# main.net
KiCad netlist of a schematic drawn in Altium Designer
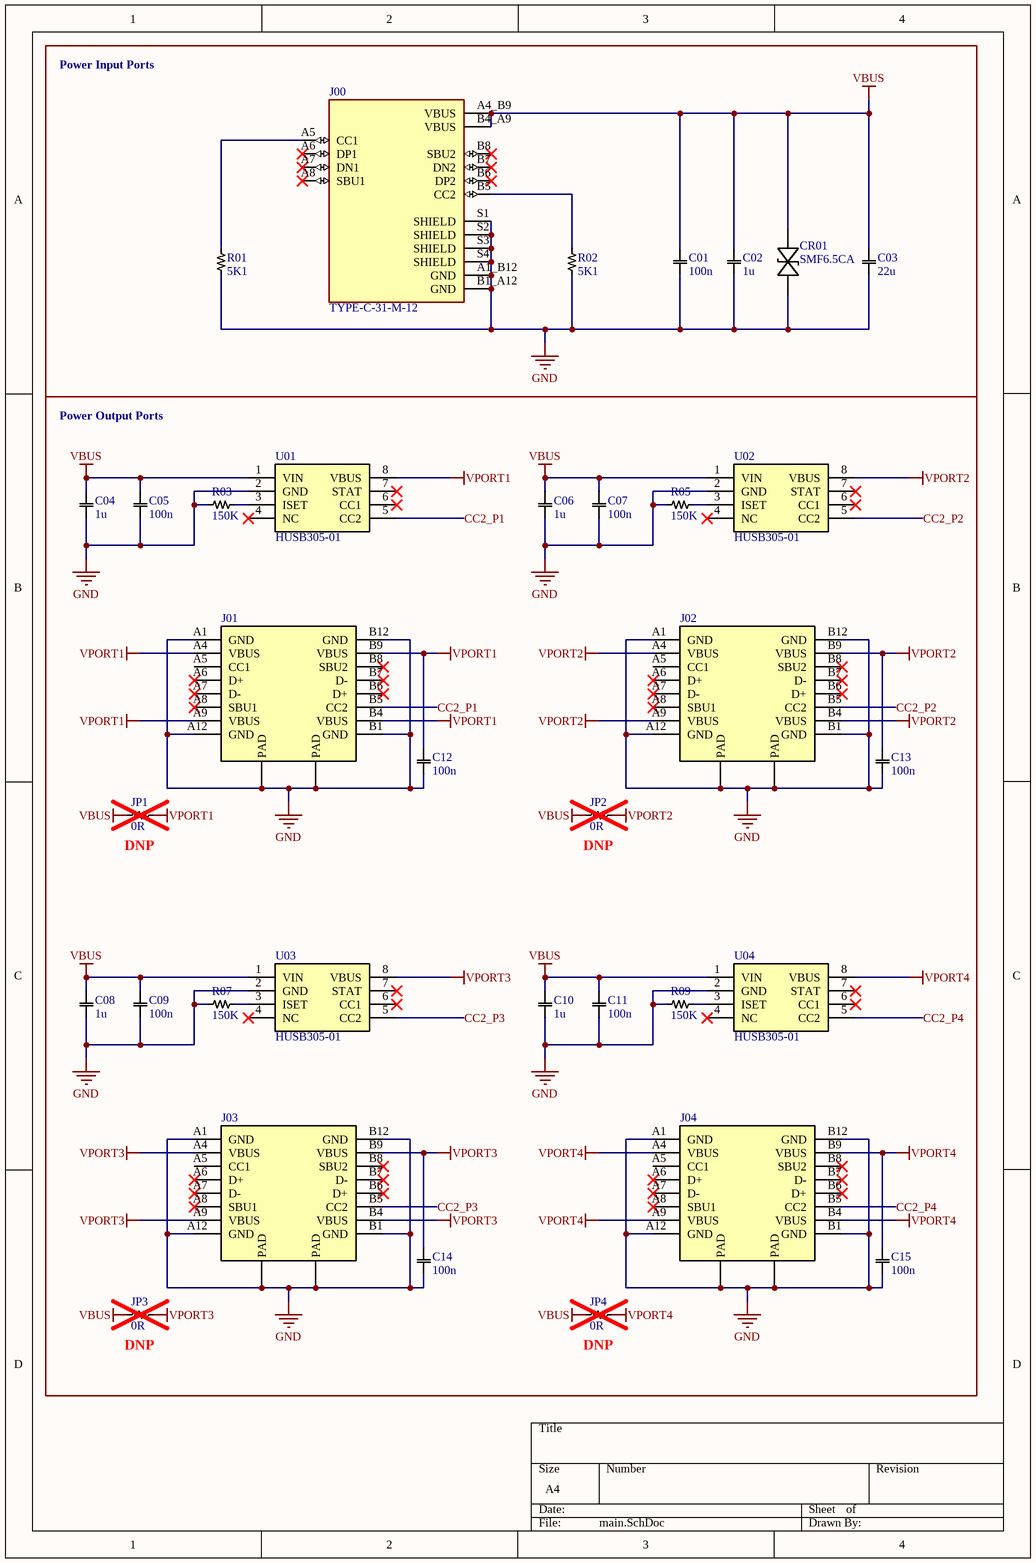
[diagram p0: main.SchDoc]

(export (version "E")
  (design (tool "Eeschema 10.0.6"))
  (components
    (comp (ref "C01")
      (value "100n")
      (footprint "RC0603N_YAG")
      (fields
        (field (name "MANUFACTURER_PART_NUMBER") "RC0603FR-0747KL")
        (field (name "COPYRIGHT") "Copyright (C) 2025 Ultra Librarian. All rights reserved.")
      )
      (libsource (lib "charge_hub_V1") (part "Capacitor"))
    )
    (comp (ref "C02")
      (value "1u")
      (footprint "RC0603N_YAG")
      (fields
        (field (name "MANUFACTURER_PART_NUMBER") "RC0603FR-0747KL")
        (field (name "COPYRIGHT") "Copyright (C) 2025 Ultra Librarian. All rights reserved.")
      )
      (libsource (lib "charge_hub_V1") (part "Capacitor"))
    )
    (comp (ref "C03")
      (value "22u")
      (footprint "RC1210")
      (fields
        (field (name "MANUFACTURER_PART_NUMBER") "RC0603FR-0747KL")
        (field (name "COPYRIGHT") "Copyright (C) 2025 Ultra Librarian. All rights reserved.")
      )
      (libsource (lib "charge_hub_V1") (part "Capacitor"))
    )
    (comp (ref "C04")
      (value "1u")
      (footprint "RC0603N_YAG")
      (fields
        (field (name "MANUFACTURER_PART_NUMBER") "RC0603FR-0747KL")
        (field (name "COPYRIGHT") "Copyright (C) 2025 Ultra Librarian. All rights reserved.")
      )
      (libsource (lib "charge_hub_V1") (part "Capacitor"))
    )
    (comp (ref "C05")
      (value "100n")
      (footprint "RC0603N_YAG")
      (fields
        (field (name "MANUFACTURER_PART_NUMBER") "RC0603FR-0747KL")
        (field (name "COPYRIGHT") "Copyright (C) 2025 Ultra Librarian. All rights reserved.")
      )
      (libsource (lib "charge_hub_V1") (part "Capacitor"))
    )
    (comp (ref "C06")
      (value "1u")
      (footprint "RC0603N_YAG")
      (fields
        (field (name "MANUFACTURER_PART_NUMBER") "RC0603FR-0747KL")
        (field (name "COPYRIGHT") "Copyright (C) 2025 Ultra Librarian. All rights reserved.")
      )
      (libsource (lib "charge_hub_V1") (part "Capacitor"))
    )
    (comp (ref "C07")
      (value "100n")
      (footprint "RC0603N_YAG")
      (fields
        (field (name "MANUFACTURER_PART_NUMBER") "RC0603FR-0747KL")
        (field (name "COPYRIGHT") "Copyright (C) 2025 Ultra Librarian. All rights reserved.")
      )
      (libsource (lib "charge_hub_V1") (part "Capacitor"))
    )
    (comp (ref "C08")
      (value "1u")
      (footprint "RC0603N_YAG")
      (fields
        (field (name "MANUFACTURER_PART_NUMBER") "RC0603FR-0747KL")
        (field (name "COPYRIGHT") "Copyright (C) 2025 Ultra Librarian. All rights reserved.")
      )
      (libsource (lib "charge_hub_V1") (part "Capacitor"))
    )
    (comp (ref "C09")
      (value "100n")
      (footprint "RC0603N_YAG")
      (fields
        (field (name "MANUFACTURER_PART_NUMBER") "RC0603FR-0747KL")
        (field (name "COPYRIGHT") "Copyright (C) 2025 Ultra Librarian. All rights reserved.")
      )
      (libsource (lib "charge_hub_V1") (part "Capacitor"))
    )
    (comp (ref "C10")
      (value "1u")
      (footprint "RC0603N_YAG")
      (fields
        (field (name "MANUFACTURER_PART_NUMBER") "RC0603FR-0747KL")
        (field (name "COPYRIGHT") "Copyright (C) 2025 Ultra Librarian. All rights reserved.")
      )
      (libsource (lib "charge_hub_V1") (part "Capacitor"))
    )
    (comp (ref "C11")
      (value "100n")
      (footprint "RC0603N_YAG")
      (fields
        (field (name "MANUFACTURER_PART_NUMBER") "RC0603FR-0747KL")
        (field (name "COPYRIGHT") "Copyright (C) 2025 Ultra Librarian. All rights reserved.")
      )
      (libsource (lib "charge_hub_V1") (part "Capacitor"))
    )
    (comp (ref "C12")
      (value "100n")
      (footprint "RC0603N_YAG")
      (fields
        (field (name "MANUFACTURER_PART_NUMBER") "RC0603FR-0747KL")
        (field (name "COPYRIGHT") "Copyright (C) 2025 Ultra Librarian. All rights reserved.")
      )
      (libsource (lib "charge_hub_V1") (part "Capacitor"))
    )
    (comp (ref "C13")
      (value "100n")
      (footprint "RC0603N_YAG")
      (fields
        (field (name "MANUFACTURER_PART_NUMBER") "RC0603FR-0747KL")
        (field (name "COPYRIGHT") "Copyright (C) 2025 Ultra Librarian. All rights reserved.")
      )
      (libsource (lib "charge_hub_V1") (part "Capacitor"))
    )
    (comp (ref "C14")
      (value "100n")
      (footprint "RC0603N_YAG")
      (fields
        (field (name "MANUFACTURER_PART_NUMBER") "RC0603FR-0747KL")
        (field (name "COPYRIGHT") "Copyright (C) 2025 Ultra Librarian. All rights reserved.")
      )
      (libsource (lib "charge_hub_V1") (part "Capacitor"))
    )
    (comp (ref "C15")
      (value "100n")
      (footprint "RC0603N_YAG")
      (fields
        (field (name "MANUFACTURER_PART_NUMBER") "RC0603FR-0747KL")
        (field (name "COPYRIGHT") "Copyright (C) 2025 Ultra Librarian. All rights reserved.")
      )
      (libsource (lib "charge_hub_V1") (part "Capacitor"))
    )
    (comp (ref "CR01")
      (value "SMF6.5CA")
      (footprint "SOD-123F_LTF")
      (description "Description")
      (fields (field (name "COPYRIGHT") "Copyright (C) 2026 Ultra Librarian. All rights reserved."))
      (libsource (lib "charge_hub_V1") (part "SMF6.5CA"))
    )
    (comp (ref "J00")
      (value "TYPE-C-31-M-12")
      (footprint "HRO_TYPE-C-31-M-12")
      (description "USB Connectors 24 Receptacle 1 8.94*7.3mm RoHS")
      (fields (field (name "MF") "HRO Electronics Co., Ltd."))
      (libsource (lib "TYPE-C-31-M-12") (part "TYPE-C-31-M-12"))
    )
    (comp (ref "J01")
      (value "TYPE-C MALE")
      (footprint "TYPE-C MALE")
      (libsource (lib "SMF6P5CA") (part "TYPE-C MALE"))
    )
    (comp (ref "J02")
      (value "TYPE-C MALE")
      (footprint "TYPE-C MALE")
      (libsource (lib "SMF6P5CA") (part "TYPE-C MALE"))
    )
    (comp (ref "J03")
      (value "TYPE-C MALE")
      (footprint "TYPE-C MALE")
      (libsource (lib "SMF6P5CA") (part "TYPE-C MALE"))
    )
    (comp (ref "J04")
      (value "TYPE-C MALE")
      (footprint "TYPE-C MALE")
      (libsource (lib "SMF6P5CA") (part "TYPE-C MALE"))
    )
    (comp (ref "JP1")
      (value "0R")
      (footprint "RC0603N_YAG")
      (description "RES SMD 47K OHM 1% 1/10W 0603")
      (fields
        (field (name "MANUFACTURER_PART_NUMBER") "RC0603FR-0747KL")
        (field (name "COPYRIGHT") "Copyright (C) 2025 Ultra Librarian. All rights reserved.")
      )
      (libsource (lib "charge_hub_V1") (part "RC0603"))
    )
    (comp (ref "JP2")
      (value "0R")
      (footprint "RC0603N_YAG")
      (description "RES SMD 47K OHM 1% 1/10W 0603")
      (fields
        (field (name "MANUFACTURER_PART_NUMBER") "RC0603FR-0747KL")
        (field (name "COPYRIGHT") "Copyright (C) 2025 Ultra Librarian. All rights reserved.")
      )
      (libsource (lib "charge_hub_V1") (part "RC0603"))
    )
    (comp (ref "JP3")
      (value "0R")
      (footprint "RC0603N_YAG")
      (description "RES SMD 47K OHM 1% 1/10W 0603")
      (fields
        (field (name "MANUFACTURER_PART_NUMBER") "RC0603FR-0747KL")
        (field (name "COPYRIGHT") "Copyright (C) 2025 Ultra Librarian. All rights reserved.")
      )
      (libsource (lib "charge_hub_V1") (part "RC0603"))
    )
    (comp (ref "JP4")
      (value "0R")
      (footprint "RC0603N_YAG")
      (description "RES SMD 47K OHM 1% 1/10W 0603")
      (fields
        (field (name "MANUFACTURER_PART_NUMBER") "RC0603FR-0747KL")
        (field (name "COPYRIGHT") "Copyright (C) 2025 Ultra Librarian. All rights reserved.")
      )
      (libsource (lib "charge_hub_V1") (part "RC0603"))
    )
    (comp (ref "R01")
      (value "5K1")
      (footprint "RC0603N_YAG")
      (description "RES SMD 47K OHM 1% 1/10W 0603")
      (fields
        (field (name "MANUFACTURER_PART_NUMBER") "RC0603FR-0747KL")
        (field (name "COPYRIGHT") "Copyright (C) 2025 Ultra Librarian. All rights reserved.")
      )
      (libsource (lib "charge_hub_V1") (part "RC0603"))
    )
    (comp (ref "R02")
      (value "5K1")
      (footprint "RC0603N_YAG")
      (description "RES SMD 47K OHM 1% 1/10W 0603")
      (fields
        (field (name "MANUFACTURER_PART_NUMBER") "RC0603FR-0747KL")
        (field (name "COPYRIGHT") "Copyright (C) 2025 Ultra Librarian. All rights reserved.")
      )
      (libsource (lib "charge_hub_V1") (part "RC0603"))
    )
    (comp (ref "R03")
      (value "150K")
      (footprint "RC0603N_YAG")
      (description "RES SMD 47K OHM 1% 1/10W 0603")
      (fields
        (field (name "MANUFACTURER_PART_NUMBER") "RC0603FR-0747KL")
        (field (name "COPYRIGHT") "Copyright (C) 2025 Ultra Librarian. All rights reserved.")
      )
      (libsource (lib "charge_hub_V1") (part "RC0603"))
    )
    (comp (ref "R05")
      (value "150K")
      (footprint "RC0603N_YAG")
      (description "RES SMD 47K OHM 1% 1/10W 0603")
      (fields
        (field (name "MANUFACTURER_PART_NUMBER") "RC0603FR-0747KL")
        (field (name "COPYRIGHT") "Copyright (C) 2025 Ultra Librarian. All rights reserved.")
      )
      (libsource (lib "charge_hub_V1") (part "RC0603"))
    )
    (comp (ref "R07")
      (value "150K")
      (footprint "RC0603N_YAG")
      (description "RES SMD 47K OHM 1% 1/10W 0603")
      (fields
        (field (name "MANUFACTURER_PART_NUMBER") "RC0603FR-0747KL")
        (field (name "COPYRIGHT") "Copyright (C) 2025 Ultra Librarian. All rights reserved.")
      )
      (libsource (lib "charge_hub_V1") (part "RC0603"))
    )
    (comp (ref "R09")
      (value "150K")
      (footprint "RC0603N_YAG")
      (description "RES SMD 47K OHM 1% 1/10W 0603")
      (fields
        (field (name "MANUFACTURER_PART_NUMBER") "RC0603FR-0747KL")
        (field (name "COPYRIGHT") "Copyright (C) 2025 Ultra Librarian. All rights reserved.")
      )
      (libsource (lib "charge_hub_V1") (part "RC0603"))
    )
    (comp (ref "U01")
      (value "HUSB305-01")
      (footprint "TSOT23-8L")
      (libsource (lib "charge_hub_V1") (part "HUSB305-01"))
    )
    (comp (ref "U02")
      (value "HUSB305-01")
      (footprint "TSOT23-8L")
      (libsource (lib "charge_hub_V1") (part "HUSB305-01"))
    )
    (comp (ref "U03")
      (value "HUSB305-01")
      (footprint "TSOT23-8L")
      (libsource (lib "charge_hub_V1") (part "HUSB305-01"))
    )
    (comp (ref "U04")
      (value "HUSB305-01")
      (footprint "TSOT23-8L")
      (libsource (lib "charge_hub_V1") (part "HUSB305-01"))
    )
  )
  (nets
    (net (code "1") (name "/CC2_P1") (class "Default")
      (node (ref "J01") (pin "B5") (pinfunction "CC2_B5") (pintype "passive"))
      (node (ref "U01") (pin "5") (pinfunction "CC2_5") (pintype "passive"))
    )
    (net (code "2") (name "/CC2_P2") (class "Default")
      (node (ref "J02") (pin "B5") (pinfunction "CC2_B5") (pintype "passive"))
      (node (ref "U02") (pin "5") (pinfunction "CC2_5") (pintype "passive"))
    )
    (net (code "3") (name "/CC2_P3") (class "Default")
      (node (ref "J03") (pin "B5") (pinfunction "CC2_B5") (pintype "passive"))
      (node (ref "U03") (pin "5") (pinfunction "CC2_5") (pintype "passive"))
    )
    (net (code "4") (name "/CC2_P4") (class "Default")
      (node (ref "J04") (pin "B5") (pinfunction "CC2_B5") (pintype "passive"))
      (node (ref "U04") (pin "5") (pinfunction "CC2_5") (pintype "passive"))
    )
    (net (code "5") (name "GND") (class "Default")
      (node (ref "C01") (pin "2") (pinfunction "2_2") (pintype "passive"))
      (node (ref "C02") (pin "2") (pinfunction "2_2") (pintype "passive"))
      (node (ref "C03") (pin "2") (pinfunction "2_2") (pintype "passive"))
      (node (ref "C04") (pin "2") (pinfunction "2_2") (pintype "passive"))
      (node (ref "C05") (pin "2") (pinfunction "2_2") (pintype "passive"))
      (node (ref "C06") (pin "2") (pinfunction "2_2") (pintype "passive"))
      (node (ref "C07") (pin "2") (pinfunction "2_2") (pintype "passive"))
      (node (ref "C08") (pin "2") (pinfunction "2_2") (pintype "passive"))
      (node (ref "C09") (pin "2") (pinfunction "2_2") (pintype "passive"))
      (node (ref "C10") (pin "2") (pinfunction "2_2") (pintype "passive"))
      (node (ref "C11") (pin "2") (pinfunction "2_2") (pintype "passive"))
      (node (ref "C12") (pin "2") (pinfunction "2_2") (pintype "passive"))
      (node (ref "C13") (pin "2") (pinfunction "2_2") (pintype "passive"))
      (node (ref "C14") (pin "2") (pinfunction "2_2") (pintype "passive"))
      (node (ref "C15") (pin "2") (pinfunction "2_2") (pintype "passive"))
      (node (ref "CR01") (pin "2") (pinfunction "2_2") (pintype "passive"))
      (node (ref "J00") (pin "A1_B12") (pinfunction "GND_A1_B12") (pintype "power_in"))
      (node (ref "J00") (pin "B1_A12") (pinfunction "GND_B1_A12") (pintype "power_in"))
      (node (ref "J00") (pin "S1") (pinfunction "SHIELD_S1") (pintype "passive"))
      (node (ref "J00") (pin "S2") (pinfunction "SHIELD_S2") (pintype "passive"))
      (node (ref "J00") (pin "S3") (pinfunction "SHIELD_S3") (pintype "passive"))
      (node (ref "J00") (pin "S4") (pinfunction "SHIELD_S4") (pintype "passive"))
      (node (ref "J01") (pin "A1") (pinfunction "GND_A1") (pintype "passive"))
      (node (ref "J01") (pin "A12") (pinfunction "GND_A12") (pintype "passive"))
      (node (ref "J01") (pin "B1") (pinfunction "GND_B1") (pintype "passive"))
      (node (ref "J01") (pin "B12") (pinfunction "GND_B12") (pintype "passive"))
      (node (ref "J01") (pin "P1") (pinfunction "PAD_P1") (pintype "passive"))
      (node (ref "J01") (pin "P2") (pinfunction "PAD_P2") (pintype "passive"))
      (node (ref "J02") (pin "A1") (pinfunction "GND_A1") (pintype "passive"))
      (node (ref "J02") (pin "A12") (pinfunction "GND_A12") (pintype "passive"))
      (node (ref "J02") (pin "B1") (pinfunction "GND_B1") (pintype "passive"))
      (node (ref "J02") (pin "B12") (pinfunction "GND_B12") (pintype "passive"))
      (node (ref "J02") (pin "P1") (pinfunction "PAD_P1") (pintype "passive"))
      (node (ref "J02") (pin "P2") (pinfunction "PAD_P2") (pintype "passive"))
      (node (ref "J03") (pin "A1") (pinfunction "GND_A1") (pintype "passive"))
      (node (ref "J03") (pin "A12") (pinfunction "GND_A12") (pintype "passive"))
      (node (ref "J03") (pin "B1") (pinfunction "GND_B1") (pintype "passive"))
      (node (ref "J03") (pin "B12") (pinfunction "GND_B12") (pintype "passive"))
      (node (ref "J03") (pin "P1") (pinfunction "PAD_P1") (pintype "passive"))
      (node (ref "J03") (pin "P2") (pinfunction "PAD_P2") (pintype "passive"))
      (node (ref "J04") (pin "A1") (pinfunction "GND_A1") (pintype "passive"))
      (node (ref "J04") (pin "A12") (pinfunction "GND_A12") (pintype "passive"))
      (node (ref "J04") (pin "B1") (pinfunction "GND_B1") (pintype "passive"))
      (node (ref "J04") (pin "B12") (pinfunction "GND_B12") (pintype "passive"))
      (node (ref "J04") (pin "P1") (pinfunction "PAD_P1") (pintype "passive"))
      (node (ref "J04") (pin "P2") (pinfunction "PAD_P2") (pintype "passive"))
      (node (ref "R01") (pin "2") (pinfunction "2_2") (pintype "passive"))
      (node (ref "R02") (pin "2") (pinfunction "2_2") (pintype "passive"))
      (node (ref "R03") (pin "1") (pinfunction "1_1") (pintype "passive"))
      (node (ref "R05") (pin "1") (pinfunction "1_1") (pintype "passive"))
      (node (ref "R07") (pin "1") (pinfunction "1_1") (pintype "passive"))
      (node (ref "R09") (pin "1") (pinfunction "1_1") (pintype "passive"))
      (node (ref "U01") (pin "2") (pinfunction "GND_2") (pintype "passive"))
      (node (ref "U02") (pin "2") (pinfunction "GND_2") (pintype "passive"))
      (node (ref "U03") (pin "2") (pinfunction "GND_2") (pintype "passive"))
      (node (ref "U04") (pin "2") (pinfunction "GND_2") (pintype "passive"))
    )
    (net (code "6") (name "Net-(J00-CC1)") (class "Default")
      (node (ref "J00") (pin "A5") (pinfunction "CC1_A5") (pintype "bidirectional"))
      (node (ref "R01") (pin "1") (pinfunction "1_1") (pintype "passive"))
    )
    (net (code "7") (name "Net-(J00-CC2)") (class "Default")
      (node (ref "J00") (pin "B5") (pinfunction "CC2_B5") (pintype "bidirectional"))
      (node (ref "R02") (pin "1") (pinfunction "1_1") (pintype "passive"))
    )
    (net (code "8") (name "Net-(U01-ISET)") (class "Default")
      (node (ref "R03") (pin "2") (pinfunction "2_2") (pintype "passive"))
      (node (ref "U01") (pin "3") (pinfunction "ISET_3") (pintype "passive"))
    )
    (net (code "9") (name "Net-(U02-ISET)") (class "Default")
      (node (ref "R05") (pin "2") (pinfunction "2_2") (pintype "passive"))
      (node (ref "U02") (pin "3") (pinfunction "ISET_3") (pintype "passive"))
    )
    (net (code "10") (name "Net-(U03-ISET)") (class "Default")
      (node (ref "R07") (pin "2") (pinfunction "2_2") (pintype "passive"))
      (node (ref "U03") (pin "3") (pinfunction "ISET_3") (pintype "passive"))
    )
    (net (code "11") (name "Net-(U04-ISET)") (class "Default")
      (node (ref "R09") (pin "2") (pinfunction "2_2") (pintype "passive"))
      (node (ref "U04") (pin "3") (pinfunction "ISET_3") (pintype "passive"))
    )
    (net (code "12") (name "VBUS") (class "Default")
      (node (ref "C01") (pin "1") (pinfunction "1_1") (pintype "passive"))
      (node (ref "C02") (pin "1") (pinfunction "1_1") (pintype "passive"))
      (node (ref "C03") (pin "1") (pinfunction "1_1") (pintype "passive"))
      (node (ref "C04") (pin "1") (pinfunction "1_1") (pintype "passive"))
      (node (ref "C05") (pin "1") (pinfunction "1_1") (pintype "passive"))
      (node (ref "C06") (pin "1") (pinfunction "1_1") (pintype "passive"))
      (node (ref "C07") (pin "1") (pinfunction "1_1") (pintype "passive"))
      (node (ref "C08") (pin "1") (pinfunction "1_1") (pintype "passive"))
      (node (ref "C09") (pin "1") (pinfunction "1_1") (pintype "passive"))
      (node (ref "C10") (pin "1") (pinfunction "1_1") (pintype "passive"))
      (node (ref "C11") (pin "1") (pinfunction "1_1") (pintype "passive"))
      (node (ref "CR01") (pin "1") (pinfunction "1_1") (pintype "passive"))
      (node (ref "J00") (pin "A4_B9") (pinfunction "VBUS_A4_B9") (pintype "power_in"))
      (node (ref "J00") (pin "B4_A9") (pinfunction "VBUS_B4_A9") (pintype "power_in"))
      (node (ref "JP1") (pin "1") (pinfunction "1_1") (pintype "passive"))
      (node (ref "JP2") (pin "1") (pinfunction "1_1") (pintype "passive"))
      (node (ref "JP3") (pin "1") (pinfunction "1_1") (pintype "passive"))
      (node (ref "JP4") (pin "1") (pinfunction "1_1") (pintype "passive"))
      (node (ref "U01") (pin "1") (pinfunction "VIN_1") (pintype "passive"))
      (node (ref "U02") (pin "1") (pinfunction "VIN_1") (pintype "passive"))
      (node (ref "U03") (pin "1") (pinfunction "VIN_1") (pintype "passive"))
      (node (ref "U04") (pin "1") (pinfunction "VIN_1") (pintype "passive"))
    )
    (net (code "13") (name "VPORT1") (class "Default")
      (node (ref "C12") (pin "1") (pinfunction "1_1") (pintype "passive"))
      (node (ref "J01") (pin "A4") (pinfunction "VBUS_A4") (pintype "passive"))
      (node (ref "J01") (pin "A9") (pinfunction "VBUS_A9") (pintype "passive"))
      (node (ref "J01") (pin "B4") (pinfunction "VBUS_B4") (pintype "passive"))
      (node (ref "J01") (pin "B9") (pinfunction "VBUS_B9") (pintype "passive"))
      (node (ref "JP1") (pin "2") (pinfunction "2_2") (pintype "passive"))
      (node (ref "U01") (pin "8") (pinfunction "VBUS_8") (pintype "passive"))
    )
    (net (code "14") (name "VPORT2") (class "Default")
      (node (ref "C13") (pin "1") (pinfunction "1_1") (pintype "passive"))
      (node (ref "J02") (pin "A4") (pinfunction "VBUS_A4") (pintype "passive"))
      (node (ref "J02") (pin "A9") (pinfunction "VBUS_A9") (pintype "passive"))
      (node (ref "J02") (pin "B4") (pinfunction "VBUS_B4") (pintype "passive"))
      (node (ref "J02") (pin "B9") (pinfunction "VBUS_B9") (pintype "passive"))
      (node (ref "JP2") (pin "2") (pinfunction "2_2") (pintype "passive"))
      (node (ref "U02") (pin "8") (pinfunction "VBUS_8") (pintype "passive"))
    )
    (net (code "15") (name "VPORT3") (class "Default")
      (node (ref "C14") (pin "1") (pinfunction "1_1") (pintype "passive"))
      (node (ref "J03") (pin "A4") (pinfunction "VBUS_A4") (pintype "passive"))
      (node (ref "J03") (pin "A9") (pinfunction "VBUS_A9") (pintype "passive"))
      (node (ref "J03") (pin "B4") (pinfunction "VBUS_B4") (pintype "passive"))
      (node (ref "J03") (pin "B9") (pinfunction "VBUS_B9") (pintype "passive"))
      (node (ref "JP3") (pin "2") (pinfunction "2_2") (pintype "passive"))
      (node (ref "U03") (pin "8") (pinfunction "VBUS_8") (pintype "passive"))
    )
    (net (code "16") (name "VPORT4") (class "Default")
      (node (ref "C15") (pin "1") (pinfunction "1_1") (pintype "passive"))
      (node (ref "J04") (pin "A4") (pinfunction "VBUS_A4") (pintype "passive"))
      (node (ref "J04") (pin "A9") (pinfunction "VBUS_A9") (pintype "passive"))
      (node (ref "J04") (pin "B4") (pinfunction "VBUS_B4") (pintype "passive"))
      (node (ref "J04") (pin "B9") (pinfunction "VBUS_B9") (pintype "passive"))
      (node (ref "JP4") (pin "2") (pinfunction "2_2") (pintype "passive"))
      (node (ref "U04") (pin "8") (pinfunction "VBUS_8") (pintype "passive"))
    )
    (net (code "17") (name "unconnected-(J00-DN1-PadA7)") (class "Default")
      (node (ref "J00") (pin "A7") (pinfunction "DN1_A7") (pintype "bidirectional+no_connect"))
    )
    (net (code "18") (name "unconnected-(J00-DN2-PadB7)") (class "Default")
      (node (ref "J00") (pin "B7") (pinfunction "DN2_B7") (pintype "bidirectional+no_connect"))
    )
    (net (code "19") (name "unconnected-(J00-DP1-PadA6)") (class "Default")
      (node (ref "J00") (pin "A6") (pinfunction "DP1_A6") (pintype "bidirectional+no_connect"))
    )
    (net (code "20") (name "unconnected-(J00-DP2-PadB6)") (class "Default")
      (node (ref "J00") (pin "B6") (pinfunction "DP2_B6") (pintype "bidirectional+no_connect"))
    )
    (net (code "21") (name "unconnected-(J00-SBU1-PadA8)") (class "Default")
      (node (ref "J00") (pin "A8") (pinfunction "SBU1_A8") (pintype "bidirectional+no_connect"))
    )
    (net (code "22") (name "unconnected-(J00-SBU2-PadB8)") (class "Default")
      (node (ref "J00") (pin "B8") (pinfunction "SBU2_B8") (pintype "bidirectional+no_connect"))
    )
    (net (code "23") (name "unconnected-(J01-CC1-PadA5)") (class "Default")
      (node (ref "J01") (pin "A5") (pinfunction "CC1_A5") (pintype "passive"))
    )
    (net (code "24") (name "unconnected-(J01-D+-PadA6)") (class "Default")
      (node (ref "J01") (pin "A6") (pinfunction "D+_A6") (pintype "passive+no_connect"))
    )
    (net (code "25") (name "unconnected-(J01-D+-PadB6)") (class "Default")
      (node (ref "J01") (pin "B6") (pinfunction "D+_B6") (pintype "passive+no_connect"))
    )
    (net (code "26") (name "unconnected-(J01-D--PadA7)") (class "Default")
      (node (ref "J01") (pin "A7") (pinfunction "D-_A7") (pintype "passive+no_connect"))
    )
    (net (code "27") (name "unconnected-(J01-D--PadB7)") (class "Default")
      (node (ref "J01") (pin "B7") (pinfunction "D-_B7") (pintype "passive+no_connect"))
    )
    (net (code "28") (name "unconnected-(J01-SBU1-PadA8)") (class "Default")
      (node (ref "J01") (pin "A8") (pinfunction "SBU1_A8") (pintype "passive+no_connect"))
    )
    (net (code "29") (name "unconnected-(J01-SBU2-PadB8)") (class "Default")
      (node (ref "J01") (pin "B8") (pinfunction "SBU2_B8") (pintype "passive+no_connect"))
    )
    (net (code "30") (name "unconnected-(J02-CC1-PadA5)") (class "Default")
      (node (ref "J02") (pin "A5") (pinfunction "CC1_A5") (pintype "passive"))
    )
    (net (code "31") (name "unconnected-(J02-D+-PadA6)") (class "Default")
      (node (ref "J02") (pin "A6") (pinfunction "D+_A6") (pintype "passive+no_connect"))
    )
    (net (code "32") (name "unconnected-(J02-D+-PadB6)") (class "Default")
      (node (ref "J02") (pin "B6") (pinfunction "D+_B6") (pintype "passive+no_connect"))
    )
    (net (code "33") (name "unconnected-(J02-D--PadA7)") (class "Default")
      (node (ref "J02") (pin "A7") (pinfunction "D-_A7") (pintype "passive+no_connect"))
    )
    (net (code "34") (name "unconnected-(J02-D--PadB7)") (class "Default")
      (node (ref "J02") (pin "B7") (pinfunction "D-_B7") (pintype "passive+no_connect"))
    )
    (net (code "35") (name "unconnected-(J02-SBU1-PadA8)") (class "Default")
      (node (ref "J02") (pin "A8") (pinfunction "SBU1_A8") (pintype "passive+no_connect"))
    )
    (net (code "36") (name "unconnected-(J02-SBU2-PadB8)") (class "Default")
      (node (ref "J02") (pin "B8") (pinfunction "SBU2_B8") (pintype "passive+no_connect"))
    )
    (net (code "37") (name "unconnected-(J03-CC1-PadA5)") (class "Default")
      (node (ref "J03") (pin "A5") (pinfunction "CC1_A5") (pintype "passive"))
    )
    (net (code "38") (name "unconnected-(J03-D+-PadA6)") (class "Default")
      (node (ref "J03") (pin "A6") (pinfunction "D+_A6") (pintype "passive+no_connect"))
    )
    (net (code "39") (name "unconnected-(J03-D+-PadB6)") (class "Default")
      (node (ref "J03") (pin "B6") (pinfunction "D+_B6") (pintype "passive+no_connect"))
    )
    (net (code "40") (name "unconnected-(J03-D--PadA7)") (class "Default")
      (node (ref "J03") (pin "A7") (pinfunction "D-_A7") (pintype "passive+no_connect"))
    )
    (net (code "41") (name "unconnected-(J03-D--PadB7)") (class "Default")
      (node (ref "J03") (pin "B7") (pinfunction "D-_B7") (pintype "passive+no_connect"))
    )
    (net (code "42") (name "unconnected-(J03-SBU1-PadA8)") (class "Default")
      (node (ref "J03") (pin "A8") (pinfunction "SBU1_A8") (pintype "passive+no_connect"))
    )
    (net (code "43") (name "unconnected-(J03-SBU2-PadB8)") (class "Default")
      (node (ref "J03") (pin "B8") (pinfunction "SBU2_B8") (pintype "passive+no_connect"))
    )
    (net (code "44") (name "unconnected-(J04-CC1-PadA5)") (class "Default")
      (node (ref "J04") (pin "A5") (pinfunction "CC1_A5") (pintype "passive"))
    )
    (net (code "45") (name "unconnected-(J04-D+-PadA6)") (class "Default")
      (node (ref "J04") (pin "A6") (pinfunction "D+_A6") (pintype "passive+no_connect"))
    )
    (net (code "46") (name "unconnected-(J04-D+-PadB6)") (class "Default")
      (node (ref "J04") (pin "B6") (pinfunction "D+_B6") (pintype "passive+no_connect"))
    )
    (net (code "47") (name "unconnected-(J04-D--PadA7)") (class "Default")
      (node (ref "J04") (pin "A7") (pinfunction "D-_A7") (pintype "passive+no_connect"))
    )
    (net (code "48") (name "unconnected-(J04-D--PadB7)") (class "Default")
      (node (ref "J04") (pin "B7") (pinfunction "D-_B7") (pintype "passive+no_connect"))
    )
    (net (code "49") (name "unconnected-(J04-SBU1-PadA8)") (class "Default")
      (node (ref "J04") (pin "A8") (pinfunction "SBU1_A8") (pintype "passive+no_connect"))
    )
    (net (code "50") (name "unconnected-(J04-SBU2-PadB8)") (class "Default")
      (node (ref "J04") (pin "B8") (pinfunction "SBU2_B8") (pintype "passive+no_connect"))
    )
    (net (code "51") (name "unconnected-(U01-CC1-Pad6)") (class "Default")
      (node (ref "U01") (pin "6") (pinfunction "CC1_6") (pintype "passive+no_connect"))
    )
    (net (code "52") (name "unconnected-(U01-NC-Pad4)") (class "Default")
      (node (ref "U01") (pin "4") (pinfunction "NC_4") (pintype "passive+no_connect"))
    )
    (net (code "53") (name "unconnected-(U01-STAT-Pad7)") (class "Default")
      (node (ref "U01") (pin "7") (pinfunction "STAT_7") (pintype "passive+no_connect"))
    )
    (net (code "54") (name "unconnected-(U02-CC1-Pad6)") (class "Default")
      (node (ref "U02") (pin "6") (pinfunction "CC1_6") (pintype "passive+no_connect"))
    )
    (net (code "55") (name "unconnected-(U02-NC-Pad4)") (class "Default")
      (node (ref "U02") (pin "4") (pinfunction "NC_4") (pintype "passive+no_connect"))
    )
    (net (code "56") (name "unconnected-(U02-STAT-Pad7)") (class "Default")
      (node (ref "U02") (pin "7") (pinfunction "STAT_7") (pintype "passive+no_connect"))
    )
    (net (code "57") (name "unconnected-(U03-CC1-Pad6)") (class "Default")
      (node (ref "U03") (pin "6") (pinfunction "CC1_6") (pintype "passive+no_connect"))
    )
    (net (code "58") (name "unconnected-(U03-NC-Pad4)") (class "Default")
      (node (ref "U03") (pin "4") (pinfunction "NC_4") (pintype "passive+no_connect"))
    )
    (net (code "59") (name "unconnected-(U03-STAT-Pad7)") (class "Default")
      (node (ref "U03") (pin "7") (pinfunction "STAT_7") (pintype "passive+no_connect"))
    )
    (net (code "60") (name "unconnected-(U04-CC1-Pad6)") (class "Default")
      (node (ref "U04") (pin "6") (pinfunction "CC1_6") (pintype "passive+no_connect"))
    )
    (net (code "61") (name "unconnected-(U04-NC-Pad4)") (class "Default")
      (node (ref "U04") (pin "4") (pinfunction "NC_4") (pintype "passive+no_connect"))
    )
    (net (code "62") (name "unconnected-(U04-STAT-Pad7)") (class "Default")
      (node (ref "U04") (pin "7") (pinfunction "STAT_7") (pintype "passive+no_connect"))
    )
  )
)
